# Sitara_DDR.net
KiCad netlist of a schematic drawn in Altium Designer
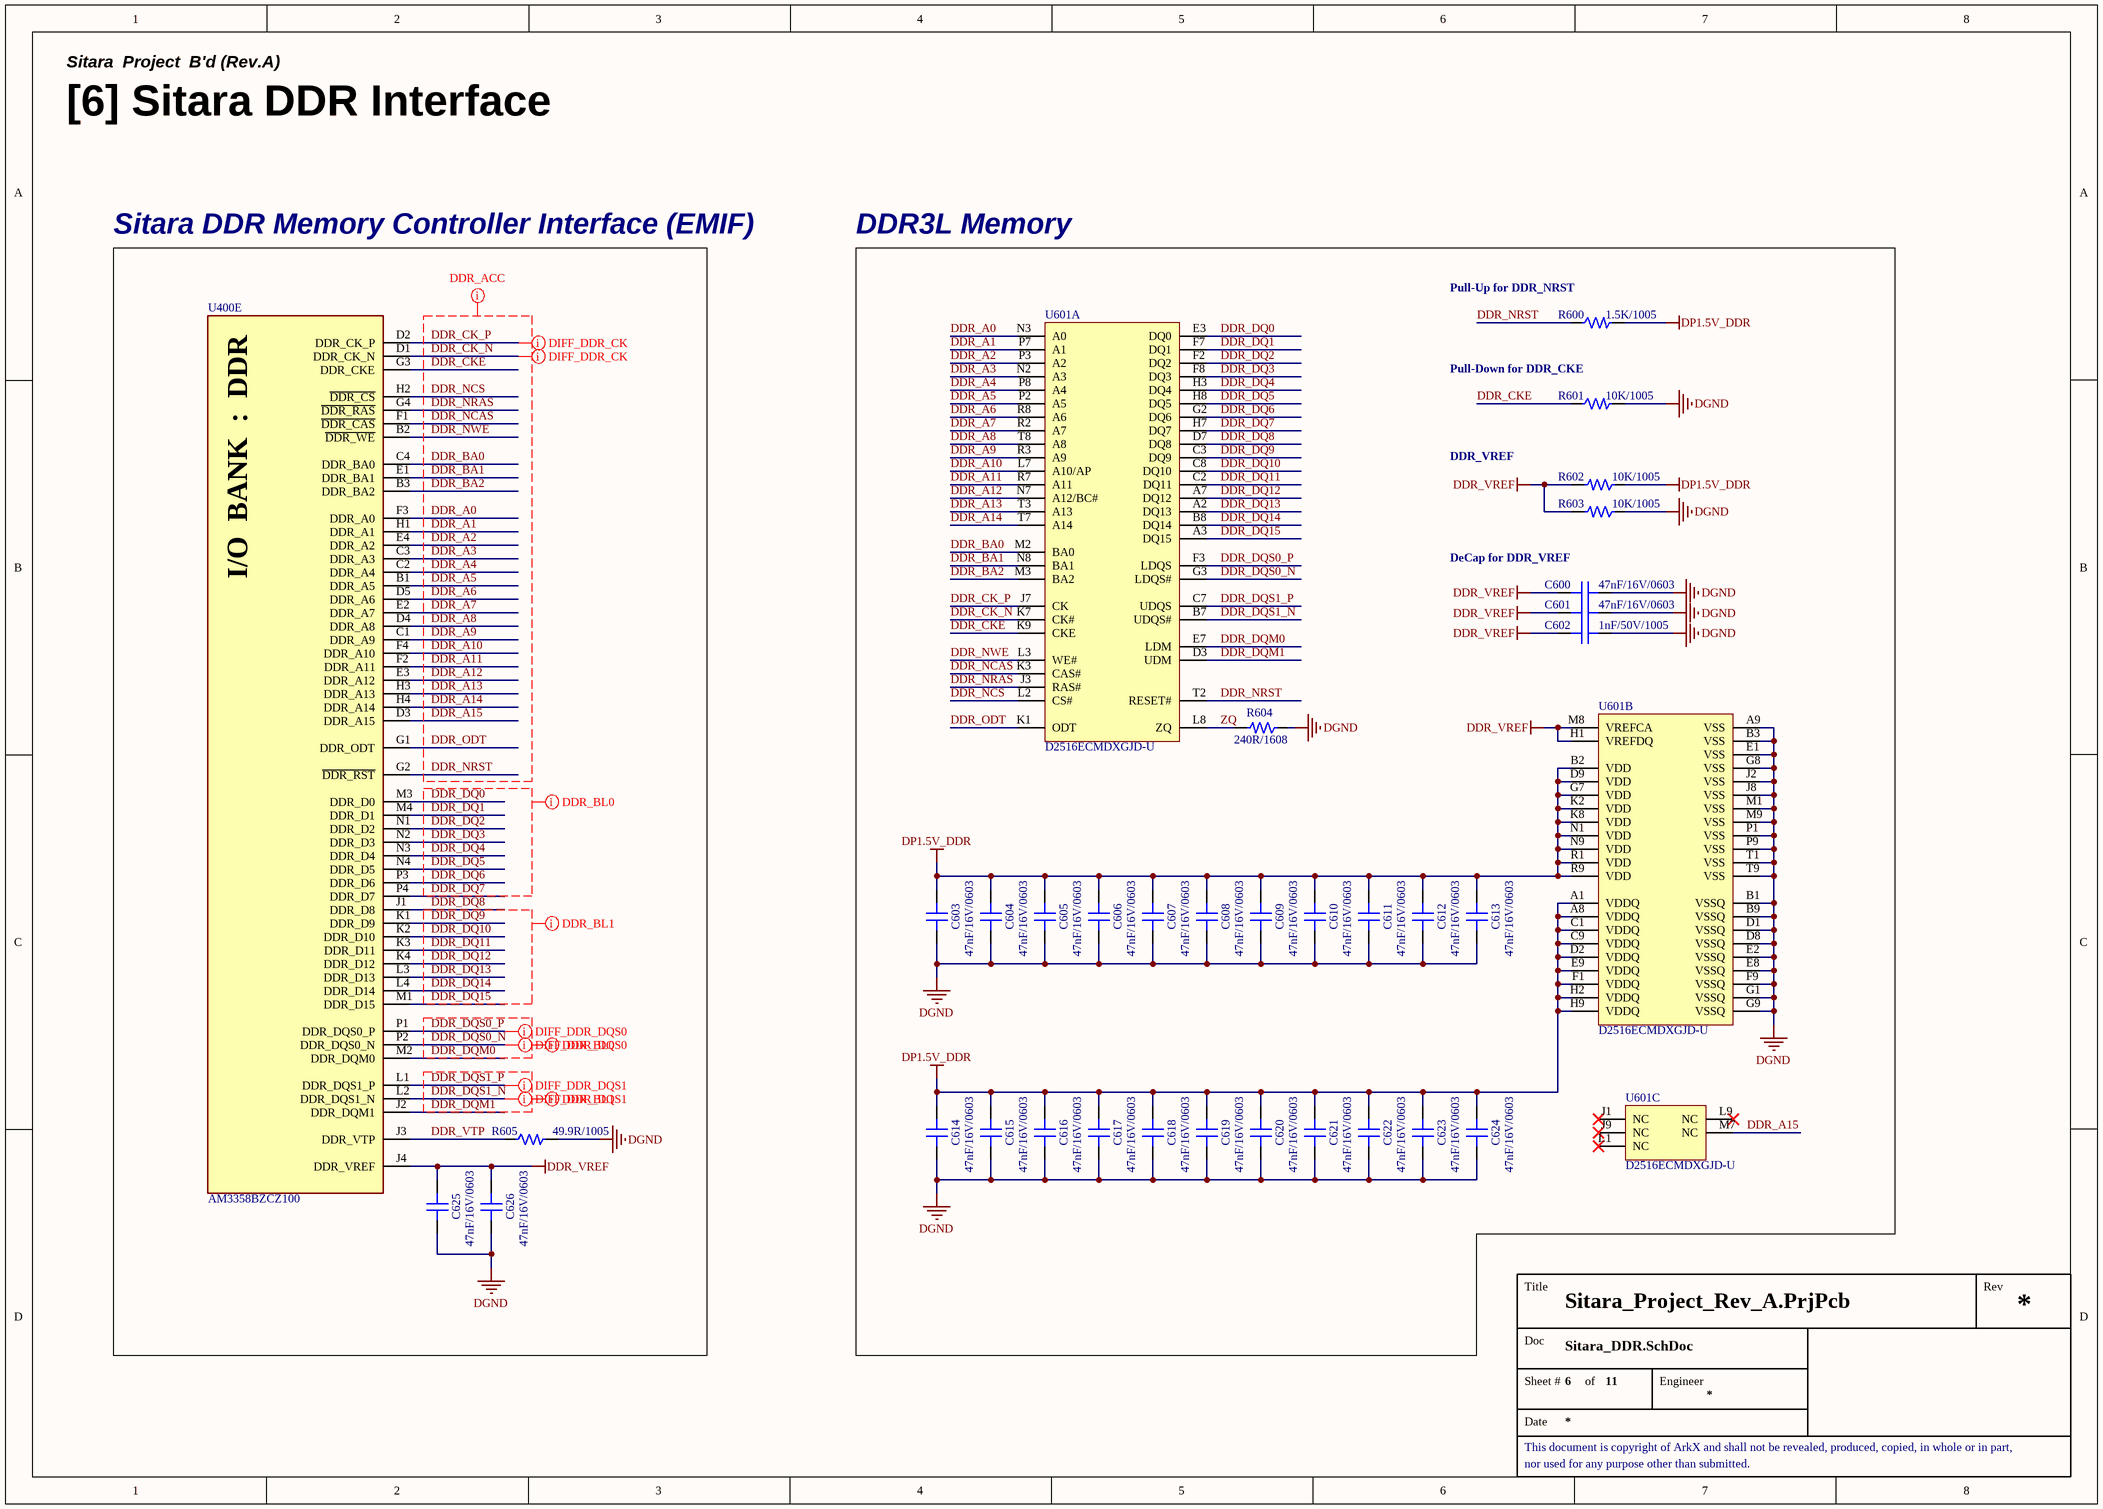
[diagram p0: Sitara_DDR.SchDoc]

(export (version "E")
  (design (tool "Eeschema 10.0.6"))
  (components
    (comp (ref "C600")
      (value "47nF/16V/0603")
      (footprint "CAP 0603 (0201_INCH)")
      (description "16V 47nF X5R ±10% 0201 Multilayer Ceramic Capacitors MLCC - SMD/SMT ROHS")
      (fields (field (name "LCSC PART #") "C88917"))
      (libsource (lib "Arkx") (part "CAP_47nF/16V/0603"))
    )
    (comp (ref "C601")
      (value "47nF/16V/0603")
      (footprint "CAP 0603 (0201_INCH)")
      (description "16V 47nF X5R ±10% 0201 Multilayer Ceramic Capacitors MLCC - SMD/SMT ROHS")
      (fields (field (name "LCSC PART #") "C88917"))
      (libsource (lib "Arkx") (part "CAP_47nF/16V/0603"))
    )
    (comp (ref "C602")
      (value "1nF/50V/1005")
      (footprint "CAP 1005 (0402_INCH)")
      (description "Ceramic CAP_1nF/50V/1005")
      (fields (field (name "LCSC PART #") "C1523"))
      (libsource (lib "Arkx") (part "CAP_1nF/50V/1005"))
    )
    (comp (ref "C603")
      (value "47nF/16V/0603")
      (footprint "CAP 0603 (0201_INCH)")
      (description "16V 47nF X5R ±10% 0201 Multilayer Ceramic Capacitors MLCC - SMD/SMT ROHS")
      (fields (field (name "LCSC PART #") "C88917"))
      (libsource (lib "Arkx") (part "CAP_47nF/16V/0603"))
    )
    (comp (ref "C604")
      (value "47nF/16V/0603")
      (footprint "CAP 0603 (0201_INCH)")
      (description "16V 47nF X5R ±10% 0201 Multilayer Ceramic Capacitors MLCC - SMD/SMT ROHS")
      (fields (field (name "LCSC PART #") "C88917"))
      (libsource (lib "Arkx") (part "CAP_47nF/16V/0603"))
    )
    (comp (ref "C605")
      (value "47nF/16V/0603")
      (footprint "CAP 0603 (0201_INCH)")
      (description "16V 47nF X5R ±10% 0201 Multilayer Ceramic Capacitors MLCC - SMD/SMT ROHS")
      (fields (field (name "LCSC PART #") "C88917"))
      (libsource (lib "Arkx") (part "CAP_47nF/16V/0603"))
    )
    (comp (ref "C606")
      (value "47nF/16V/0603")
      (footprint "CAP 0603 (0201_INCH)")
      (description "16V 47nF X5R ±10% 0201 Multilayer Ceramic Capacitors MLCC - SMD/SMT ROHS")
      (fields (field (name "LCSC PART #") "C88917"))
      (libsource (lib "Arkx") (part "CAP_47nF/16V/0603"))
    )
    (comp (ref "C607")
      (value "47nF/16V/0603")
      (footprint "CAP 0603 (0201_INCH)")
      (description "16V 47nF X5R ±10% 0201 Multilayer Ceramic Capacitors MLCC - SMD/SMT ROHS")
      (fields (field (name "LCSC PART #") "C88917"))
      (libsource (lib "Arkx") (part "CAP_47nF/16V/0603"))
    )
    (comp (ref "C608")
      (value "47nF/16V/0603")
      (footprint "CAP 0603 (0201_INCH)")
      (description "16V 47nF X5R ±10% 0201 Multilayer Ceramic Capacitors MLCC - SMD/SMT ROHS")
      (fields (field (name "LCSC PART #") "C88917"))
      (libsource (lib "Arkx") (part "CAP_47nF/16V/0603"))
    )
    (comp (ref "C609")
      (value "47nF/16V/0603")
      (footprint "CAP 0603 (0201_INCH)")
      (description "16V 47nF X5R ±10% 0201 Multilayer Ceramic Capacitors MLCC - SMD/SMT ROHS")
      (fields (field (name "LCSC PART #") "C88917"))
      (libsource (lib "Arkx") (part "CAP_47nF/16V/0603"))
    )
    (comp (ref "C610")
      (value "47nF/16V/0603")
      (footprint "CAP 0603 (0201_INCH)")
      (description "16V 47nF X5R ±10% 0201 Multilayer Ceramic Capacitors MLCC - SMD/SMT ROHS")
      (fields (field (name "LCSC PART #") "C88917"))
      (libsource (lib "Arkx") (part "CAP_47nF/16V/0603"))
    )
    (comp (ref "C611")
      (value "47nF/16V/0603")
      (footprint "CAP 0603 (0201_INCH)")
      (description "16V 47nF X5R ±10% 0201 Multilayer Ceramic Capacitors MLCC - SMD/SMT ROHS")
      (fields (field (name "LCSC PART #") "C88917"))
      (libsource (lib "Arkx") (part "CAP_47nF/16V/0603"))
    )
    (comp (ref "C612")
      (value "47nF/16V/0603")
      (footprint "CAP 0603 (0201_INCH)")
      (description "16V 47nF X5R ±10% 0201 Multilayer Ceramic Capacitors MLCC - SMD/SMT ROHS")
      (fields (field (name "LCSC PART #") "C88917"))
      (libsource (lib "Arkx") (part "CAP_47nF/16V/0603"))
    )
    (comp (ref "C613")
      (value "47nF/16V/0603")
      (footprint "CAP 0603 (0201_INCH)")
      (description "16V 47nF X5R ±10% 0201 Multilayer Ceramic Capacitors MLCC - SMD/SMT ROHS")
      (fields (field (name "LCSC PART #") "C88917"))
      (libsource (lib "Arkx") (part "CAP_47nF/16V/0603"))
    )
    (comp (ref "C614")
      (value "47nF/16V/0603")
      (footprint "CAP 0603 (0201_INCH)")
      (description "16V 47nF X5R ±10% 0201 Multilayer Ceramic Capacitors MLCC - SMD/SMT ROHS")
      (fields (field (name "LCSC PART #") "C88917"))
      (libsource (lib "Arkx") (part "CAP_47nF/16V/0603"))
    )
    (comp (ref "C615")
      (value "47nF/16V/0603")
      (footprint "CAP 0603 (0201_INCH)")
      (description "16V 47nF X5R ±10% 0201 Multilayer Ceramic Capacitors MLCC - SMD/SMT ROHS")
      (fields (field (name "LCSC PART #") "C88917"))
      (libsource (lib "Arkx") (part "CAP_47nF/16V/0603"))
    )
    (comp (ref "C616")
      (value "47nF/16V/0603")
      (footprint "CAP 0603 (0201_INCH)")
      (description "16V 47nF X5R ±10% 0201 Multilayer Ceramic Capacitors MLCC - SMD/SMT ROHS")
      (fields (field (name "LCSC PART #") "C88917"))
      (libsource (lib "Arkx") (part "CAP_47nF/16V/0603"))
    )
    (comp (ref "C617")
      (value "47nF/16V/0603")
      (footprint "CAP 0603 (0201_INCH)")
      (description "16V 47nF X5R ±10% 0201 Multilayer Ceramic Capacitors MLCC - SMD/SMT ROHS")
      (fields (field (name "LCSC PART #") "C88917"))
      (libsource (lib "Arkx") (part "CAP_47nF/16V/0603"))
    )
    (comp (ref "C618")
      (value "47nF/16V/0603")
      (footprint "CAP 0603 (0201_INCH)")
      (description "16V 47nF X5R ±10% 0201 Multilayer Ceramic Capacitors MLCC - SMD/SMT ROHS")
      (fields (field (name "LCSC PART #") "C88917"))
      (libsource (lib "Arkx") (part "CAP_47nF/16V/0603"))
    )
    (comp (ref "C619")
      (value "47nF/16V/0603")
      (footprint "CAP 0603 (0201_INCH)")
      (description "16V 47nF X5R ±10% 0201 Multilayer Ceramic Capacitors MLCC - SMD/SMT ROHS")
      (fields (field (name "LCSC PART #") "C88917"))
      (libsource (lib "Arkx") (part "CAP_47nF/16V/0603"))
    )
    (comp (ref "C620")
      (value "47nF/16V/0603")
      (footprint "CAP 0603 (0201_INCH)")
      (description "16V 47nF X5R ±10% 0201 Multilayer Ceramic Capacitors MLCC - SMD/SMT ROHS")
      (fields (field (name "LCSC PART #") "C88917"))
      (libsource (lib "Arkx") (part "CAP_47nF/16V/0603"))
    )
    (comp (ref "C621")
      (value "47nF/16V/0603")
      (footprint "CAP 0603 (0201_INCH)")
      (description "16V 47nF X5R ±10% 0201 Multilayer Ceramic Capacitors MLCC - SMD/SMT ROHS")
      (fields (field (name "LCSC PART #") "C88917"))
      (libsource (lib "Arkx") (part "CAP_47nF/16V/0603"))
    )
    (comp (ref "C622")
      (value "47nF/16V/0603")
      (footprint "CAP 0603 (0201_INCH)")
      (description "16V 47nF X5R ±10% 0201 Multilayer Ceramic Capacitors MLCC - SMD/SMT ROHS")
      (fields (field (name "LCSC PART #") "C88917"))
      (libsource (lib "Arkx") (part "CAP_47nF/16V/0603"))
    )
    (comp (ref "C623")
      (value "47nF/16V/0603")
      (footprint "CAP 0603 (0201_INCH)")
      (description "16V 47nF X5R ±10% 0201 Multilayer Ceramic Capacitors MLCC - SMD/SMT ROHS")
      (fields (field (name "LCSC PART #") "C88917"))
      (libsource (lib "Arkx") (part "CAP_47nF/16V/0603"))
    )
    (comp (ref "C624")
      (value "47nF/16V/0603")
      (footprint "CAP 0603 (0201_INCH)")
      (description "16V 47nF X5R ±10% 0201 Multilayer Ceramic Capacitors MLCC - SMD/SMT ROHS")
      (fields (field (name "LCSC PART #") "C88917"))
      (libsource (lib "Arkx") (part "CAP_47nF/16V/0603"))
    )
    (comp (ref "C625")
      (value "47nF/16V/0603")
      (footprint "CAP 0603 (0201_INCH)")
      (description "16V 47nF X5R ±10% 0201 Multilayer Ceramic Capacitors MLCC - SMD/SMT ROHS")
      (fields (field (name "LCSC PART #") "C88917"))
      (libsource (lib "Arkx") (part "CAP_47nF/16V/0603"))
    )
    (comp (ref "C626")
      (value "47nF/16V/0603")
      (footprint "CAP 0603 (0201_INCH)")
      (description "16V 47nF X5R ±10% 0201 Multilayer Ceramic Capacitors MLCC - SMD/SMT ROHS")
      (fields (field (name "LCSC PART #") "C88917"))
      (libsource (lib "Arkx") (part "CAP_47nF/16V/0603"))
    )
    (comp (ref "R600")
      (value "1.5K/1005")
      (footprint "RES 1005 (0402_inch)")
      (description "RES_1.5K/1005/62.5mW")
      (fields (field (name "LCSC PART #") "C25867"))
      (libsource (lib "Arkx") (part "RES_1.5K/1005/62.5mW"))
    )
    (comp (ref "R601")
      (value "10K/1005")
      (footprint "RES 1005 (0402_inch)")
      (description "RES_10K/1005/62.5mW")
      (fields (field (name "LCSC PART #") "C25744"))
      (libsource (lib "Arkx") (part "RES_10K/1005/62.5mW"))
    )
    (comp (ref "R602")
      (value "10K/1005")
      (footprint "RES 1005 (0402_inch)")
      (description "RES_10K/1005/62.5mW")
      (fields (field (name "LCSC PART #") "C25744"))
      (libsource (lib "Arkx") (part "RES_10K/1005/62.5mW"))
    )
    (comp (ref "R603")
      (value "10K/1005")
      (footprint "RES 1005 (0402_inch)")
      (description "RES_10K/1005/62.5mW")
      (fields (field (name "LCSC PART #") "C25744"))
      (libsource (lib "Arkx") (part "RES_10K/1005/62.5mW"))
    )
    (comp (ref "R604")
      (value "240R/1608")
      (footprint "RES 1608 (0603_inch)")
      (description "RES_240R/1608/0.1W")
      (fields (field (name "LCSC PART #") "C23350"))
      (libsource (lib "Arkx") (part "RES_240R/1608/0.1W"))
    )
    (comp (ref "R605")
      (value "49.9R/1005")
      (footprint "RES 1005 (0402_inch)")
      (description "RES_49.9R/1005/62.5mW")
      (fields (field (name "LCSC PART #") "C25120"))
      (libsource (lib "Arkx") (part "RES_49.9R/1005/62.5mW"))
    )
    (comp (ref "U400")
      (value "AM3358BZCZ100")
      (footprint "IC_SOC_AM3358BZCZ100")
      (description "ARM® Cortex®-A8 Microprocessor IC Sitara™ 1 Core, 32-Bit 1.0GHz 324-NFBGA (15x15)")
      (fields (field (name "LCSC PART #") "C73932"))
      (libsource (lib "Arkx") (part "IC_SOC_AM3358BZCZ100"))
    )
    (comp (ref "U601")
      (value "D2516ECMDXGJD-U")
      (footprint "IC_MEM_DDR3L_MT41K256M16TW-107 IT:P")
      (description "DRAM 4Gb 96 ball FBGA DDR3L 1866")
      (fields (field (name "LCSC PART #") "C2927180"))
      (libsource (lib "Arkx") (part "IC_MEM_DDR3L_D2516ECMDXGJD-U"))
    )
  )
  (nets
    (net (code "1") (name "/DDR_A0") (class "Default")
      (node (ref "U400") (pin "F3") (pinfunction "DDR_A0_F3") (pintype "passive"))
      (node (ref "U601") (pin "N3") (pinfunction "A0_N3") (pintype "passive"))
    )
    (net (code "2") (name "/DDR_A1") (class "Default")
      (node (ref "U400") (pin "H1") (pinfunction "DDR_A1_H1") (pintype "passive"))
      (node (ref "U601") (pin "P7") (pinfunction "A1_P7") (pintype "passive"))
    )
    (net (code "3") (name "/DDR_A2") (class "Default")
      (node (ref "U400") (pin "E4") (pinfunction "DDR_A2_E4") (pintype "passive"))
      (node (ref "U601") (pin "P3") (pinfunction "A2_P3") (pintype "passive"))
    )
    (net (code "4") (name "/DDR_A3") (class "Default")
      (node (ref "U400") (pin "C3") (pinfunction "DDR_A3_C3") (pintype "passive"))
      (node (ref "U601") (pin "N2") (pinfunction "A3_N2") (pintype "passive"))
    )
    (net (code "5") (name "/DDR_A4") (class "Default")
      (node (ref "U400") (pin "C2") (pinfunction "DDR_A4_C2") (pintype "passive"))
      (node (ref "U601") (pin "P8") (pinfunction "A4_P8") (pintype "passive"))
    )
    (net (code "6") (name "/DDR_A5") (class "Default")
      (node (ref "U400") (pin "B1") (pinfunction "DDR_A5_B1") (pintype "passive"))
      (node (ref "U601") (pin "P2") (pinfunction "A5_P2") (pintype "passive"))
    )
    (net (code "7") (name "/DDR_A6") (class "Default")
      (node (ref "U400") (pin "D5") (pinfunction "DDR_A6_D5") (pintype "passive"))
      (node (ref "U601") (pin "R8") (pinfunction "A6_R8") (pintype "passive"))
    )
    (net (code "8") (name "/DDR_A7") (class "Default")
      (node (ref "U400") (pin "E2") (pinfunction "DDR_A7_E2") (pintype "passive"))
      (node (ref "U601") (pin "R2") (pinfunction "A7_R2") (pintype "passive"))
    )
    (net (code "9") (name "/DDR_A8") (class "Default")
      (node (ref "U400") (pin "D4") (pinfunction "DDR_A8_D4") (pintype "passive"))
      (node (ref "U601") (pin "T8") (pinfunction "A8_T8") (pintype "passive"))
    )
    (net (code "10") (name "/DDR_A9") (class "Default")
      (node (ref "U400") (pin "C1") (pinfunction "DDR_A9_C1") (pintype "passive"))
      (node (ref "U601") (pin "R3") (pinfunction "A9_R3") (pintype "passive"))
    )
    (net (code "11") (name "/DDR_A10") (class "Default")
      (node (ref "U400") (pin "F4") (pinfunction "DDR_A10_F4") (pintype "passive"))
      (node (ref "U601") (pin "L7") (pinfunction "A10/AP_L7") (pintype "passive"))
    )
    (net (code "12") (name "/DDR_A11") (class "Default")
      (node (ref "U400") (pin "F2") (pinfunction "DDR_A11_F2") (pintype "passive"))
      (node (ref "U601") (pin "R7") (pinfunction "A11_R7") (pintype "passive"))
    )
    (net (code "13") (name "/DDR_A12") (class "Default")
      (node (ref "U400") (pin "E3") (pinfunction "DDR_A12_E3") (pintype "passive"))
      (node (ref "U601") (pin "N7") (pinfunction "A12/BC#_N7") (pintype "passive"))
    )
    (net (code "14") (name "/DDR_A13") (class "Default")
      (node (ref "U400") (pin "H3") (pinfunction "DDR_A13_H3") (pintype "passive"))
      (node (ref "U601") (pin "T3") (pinfunction "A13_T3") (pintype "passive"))
    )
    (net (code "15") (name "/DDR_A14") (class "Default")
      (node (ref "U400") (pin "H4") (pinfunction "DDR_A14_H4") (pintype "passive"))
      (node (ref "U601") (pin "T7") (pinfunction "A14_T7") (pintype "passive"))
    )
    (net (code "16") (name "/DDR_A15") (class "Default")
      (node (ref "U400") (pin "D3") (pinfunction "DDR_A15_D3") (pintype "passive"))
      (node (ref "U601") (pin "M7") (pinfunction "NC_M7") (pintype "passive"))
    )
    (net (code "17") (name "/DDR_BA0") (class "Default")
      (node (ref "U400") (pin "C4") (pinfunction "DDR_BA0_C4") (pintype "passive"))
      (node (ref "U601") (pin "M2") (pinfunction "BA0_M2") (pintype "passive"))
    )
    (net (code "18") (name "/DDR_BA1") (class "Default")
      (node (ref "U400") (pin "E1") (pinfunction "DDR_BA1_E1") (pintype "passive"))
      (node (ref "U601") (pin "N8") (pinfunction "BA1_N8") (pintype "passive"))
    )
    (net (code "19") (name "/DDR_BA2") (class "Default")
      (node (ref "U400") (pin "B3") (pinfunction "DDR_BA2_B3") (pintype "passive"))
      (node (ref "U601") (pin "M3") (pinfunction "BA2_M3") (pintype "passive"))
    )
    (net (code "20") (name "/DDR_CKE") (class "Default")
      (node (ref "R601") (pin "1") (pinfunction "1_1") (pintype "passive"))
      (node (ref "U400") (pin "G3") (pinfunction "DDR_CKE_G3") (pintype "passive"))
      (node (ref "U601") (pin "K9") (pinfunction "CKE_K9") (pintype "passive"))
    )
    (net (code "21") (name "/DDR_CK_N") (class "Default")
      (node (ref "U400") (pin "D1") (pinfunction "DDR_CK_N_D1") (pintype "passive"))
      (node (ref "U601") (pin "K7") (pinfunction "CK#_K7") (pintype "passive"))
    )
    (net (code "22") (name "/DDR_CK_P") (class "Default")
      (node (ref "U400") (pin "D2") (pinfunction "DDR_CK_P_D2") (pintype "passive"))
      (node (ref "U601") (pin "J7") (pinfunction "CK_J7") (pintype "passive"))
    )
    (net (code "23") (name "/DDR_DQ0") (class "Default")
      (node (ref "U400") (pin "M3") (pinfunction "DDR_D0_M3") (pintype "passive"))
      (node (ref "U601") (pin "E3") (pinfunction "DQ0_E3") (pintype "passive"))
    )
    (net (code "24") (name "/DDR_DQ1") (class "Default")
      (node (ref "U400") (pin "M4") (pinfunction "DDR_D1_M4") (pintype "passive"))
      (node (ref "U601") (pin "F7") (pinfunction "DQ1_F7") (pintype "passive"))
    )
    (net (code "25") (name "/DDR_DQ2") (class "Default")
      (node (ref "U400") (pin "N1") (pinfunction "DDR_D2_N1") (pintype "passive"))
      (node (ref "U601") (pin "F2") (pinfunction "DQ2_F2") (pintype "passive"))
    )
    (net (code "26") (name "/DDR_DQ3") (class "Default")
      (node (ref "U400") (pin "N2") (pinfunction "DDR_D3_N2") (pintype "passive"))
      (node (ref "U601") (pin "F8") (pinfunction "DQ3_F8") (pintype "passive"))
    )
    (net (code "27") (name "/DDR_DQ4") (class "Default")
      (node (ref "U400") (pin "N3") (pinfunction "DDR_D4_N3") (pintype "passive"))
      (node (ref "U601") (pin "H3") (pinfunction "DQ4_H3") (pintype "passive"))
    )
    (net (code "28") (name "/DDR_DQ5") (class "Default")
      (node (ref "U400") (pin "N4") (pinfunction "DDR_D5_N4") (pintype "passive"))
      (node (ref "U601") (pin "H8") (pinfunction "DQ5_H8") (pintype "passive"))
    )
    (net (code "29") (name "/DDR_DQ6") (class "Default")
      (node (ref "U400") (pin "P3") (pinfunction "DDR_D6_P3") (pintype "passive"))
      (node (ref "U601") (pin "G2") (pinfunction "DQ6_G2") (pintype "passive"))
    )
    (net (code "30") (name "/DDR_DQ7") (class "Default")
      (node (ref "U400") (pin "P4") (pinfunction "DDR_D7_P4") (pintype "passive"))
      (node (ref "U601") (pin "H7") (pinfunction "DQ7_H7") (pintype "passive"))
    )
    (net (code "31") (name "/DDR_DQ8") (class "Default")
      (node (ref "U400") (pin "J1") (pinfunction "DDR_D8_J1") (pintype "passive"))
      (node (ref "U601") (pin "D7") (pinfunction "DQ8_D7") (pintype "passive"))
    )
    (net (code "32") (name "/DDR_DQ9") (class "Default")
      (node (ref "U400") (pin "K1") (pinfunction "DDR_D9_K1") (pintype "passive"))
      (node (ref "U601") (pin "C3") (pinfunction "DQ9_C3") (pintype "passive"))
    )
    (net (code "33") (name "/DDR_DQ10") (class "Default")
      (node (ref "U400") (pin "K2") (pinfunction "DDR_D10_K2") (pintype "passive"))
      (node (ref "U601") (pin "C8") (pinfunction "DQ10_C8") (pintype "passive"))
    )
    (net (code "34") (name "/DDR_DQ11") (class "Default")
      (node (ref "U400") (pin "K3") (pinfunction "DDR_D11_K3") (pintype "passive"))
      (node (ref "U601") (pin "C2") (pinfunction "DQ11_C2") (pintype "passive"))
    )
    (net (code "35") (name "/DDR_DQ12") (class "Default")
      (node (ref "U400") (pin "K4") (pinfunction "DDR_D12_K4") (pintype "passive"))
      (node (ref "U601") (pin "A7") (pinfunction "DQ12_A7") (pintype "passive"))
    )
    (net (code "36") (name "/DDR_DQ13") (class "Default")
      (node (ref "U400") (pin "L3") (pinfunction "DDR_D13_L3") (pintype "passive"))
      (node (ref "U601") (pin "A2") (pinfunction "DQ13_A2") (pintype "passive"))
    )
    (net (code "37") (name "/DDR_DQ14") (class "Default")
      (node (ref "U400") (pin "L4") (pinfunction "DDR_D14_L4") (pintype "passive"))
      (node (ref "U601") (pin "B8") (pinfunction "DQ14_B8") (pintype "passive"))
    )
    (net (code "38") (name "/DDR_DQ15") (class "Default")
      (node (ref "U400") (pin "M1") (pinfunction "DDR_D15_M1") (pintype "passive"))
      (node (ref "U601") (pin "A3") (pinfunction "DQ15_A3") (pintype "passive"))
    )
    (net (code "39") (name "/DDR_DQM0") (class "Default")
      (node (ref "U400") (pin "M2") (pinfunction "DDR_DQM0_M2") (pintype "passive"))
      (node (ref "U601") (pin "E7") (pinfunction "LDM_E7") (pintype "passive"))
    )
    (net (code "40") (name "/DDR_DQM1") (class "Default")
      (node (ref "U400") (pin "J2") (pinfunction "DDR_DQM1_J2") (pintype "passive"))
      (node (ref "U601") (pin "D3") (pinfunction "UDM_D3") (pintype "passive"))
    )
    (net (code "41") (name "/DDR_DQS0_N") (class "Default")
      (node (ref "U400") (pin "P2") (pinfunction "DDR_DQS0_N_P2") (pintype "passive"))
      (node (ref "U601") (pin "G3") (pinfunction "LDQS#_G3") (pintype "passive"))
    )
    (net (code "42") (name "/DDR_DQS0_P") (class "Default")
      (node (ref "U400") (pin "P1") (pinfunction "DDR_DQS0_P_P1") (pintype "passive"))
      (node (ref "U601") (pin "F3") (pinfunction "LDQS_F3") (pintype "passive"))
    )
    (net (code "43") (name "/DDR_DQS1_N") (class "Default")
      (node (ref "U400") (pin "L2") (pinfunction "DDR_DQS1_N_L2") (pintype "passive"))
      (node (ref "U601") (pin "B7") (pinfunction "UDQS#_B7") (pintype "passive"))
    )
    (net (code "44") (name "/DDR_DQS1_P") (class "Default")
      (node (ref "U400") (pin "L1") (pinfunction "DDR_DQS1_P_L1") (pintype "passive"))
      (node (ref "U601") (pin "C7") (pinfunction "UDQS_C7") (pintype "passive"))
    )
    (net (code "45") (name "/DDR_NCAS") (class "Default")
      (node (ref "U400") (pin "F1") (pinfunction "~{DDR_CAS}_F1") (pintype "passive"))
      (node (ref "U601") (pin "K3") (pinfunction "CAS#_K3") (pintype "passive"))
    )
    (net (code "46") (name "/DDR_NCS") (class "Default")
      (node (ref "U400") (pin "H2") (pinfunction "~{DDR_CS}_H2") (pintype "passive"))
      (node (ref "U601") (pin "L2") (pinfunction "CS#_L2") (pintype "passive"))
    )
    (net (code "47") (name "/DDR_NRAS") (class "Default")
      (node (ref "U400") (pin "G4") (pinfunction "~{DDR_RAS}_G4") (pintype "passive"))
      (node (ref "U601") (pin "J3") (pinfunction "RAS#_J3") (pintype "passive"))
    )
    (net (code "48") (name "/DDR_NRST") (class "Default")
      (node (ref "R600") (pin "1") (pinfunction "1_1") (pintype "passive"))
      (node (ref "U400") (pin "G2") (pinfunction "~{DDR_RST}_G2") (pintype "passive"))
      (node (ref "U601") (pin "T2") (pinfunction "RESET#_T2") (pintype "passive"))
    )
    (net (code "49") (name "/DDR_NWE") (class "Default")
      (node (ref "U400") (pin "B2") (pinfunction "~{DDR_WE}_B2") (pintype "passive"))
      (node (ref "U601") (pin "L3") (pinfunction "WE#_L3") (pintype "passive"))
    )
    (net (code "50") (name "/DDR_ODT") (class "Default")
      (node (ref "U400") (pin "G1") (pinfunction "DDR_ODT_G1") (pintype "passive"))
      (node (ref "U601") (pin "K1") (pinfunction "ODT_K1") (pintype "passive"))
    )
    (net (code "51") (name "/DDR_VTP") (class "Default")
      (node (ref "R605") (pin "1") (pinfunction "1_1") (pintype "passive"))
      (node (ref "U400") (pin "J3") (pinfunction "DDR_VTP_J3") (pintype "passive"))
    )
    (net (code "52") (name "/ZQ") (class "Default")
      (node (ref "R604") (pin "2") (pinfunction "2_2") (pintype "passive"))
      (node (ref "U601") (pin "L8") (pinfunction "ZQ_L8") (pintype "passive"))
    )
    (net (code "53") (name "DDR_VREF") (class "Default")
      (node (ref "C600") (pin "2") (pinfunction "2_2") (pintype "passive"))
      (node (ref "C601") (pin "2") (pinfunction "2_2") (pintype "passive"))
      (node (ref "C602") (pin "2") (pinfunction "2_2") (pintype "passive"))
      (node (ref "C625") (pin "2") (pinfunction "2_2") (pintype "passive"))
      (node (ref "C626") (pin "2") (pinfunction "2_2") (pintype "passive"))
      (node (ref "R602") (pin "2") (pinfunction "2_2") (pintype "passive"))
      (node (ref "R603") (pin "2") (pinfunction "2_2") (pintype "passive"))
      (node (ref "U400") (pin "J4") (pinfunction "DDR_VREF_J4") (pintype "passive"))
      (node (ref "U601") (pin "H1") (pinfunction "VREFDQ_H1") (pintype "passive"))
      (node (ref "U601") (pin "M8") (pinfunction "VREFCA_M8") (pintype "passive"))
    )
    (net (code "54") (name "DGND") (class "Default")
      (node (ref "C600") (pin "1") (pinfunction "1_1") (pintype "passive"))
      (node (ref "C601") (pin "1") (pinfunction "1_1") (pintype "passive"))
      (node (ref "C602") (pin "1") (pinfunction "1_1") (pintype "passive"))
      (node (ref "C603") (pin "1") (pinfunction "1_1") (pintype "passive"))
      (node (ref "C604") (pin "1") (pinfunction "1_1") (pintype "passive"))
      (node (ref "C605") (pin "1") (pinfunction "1_1") (pintype "passive"))
      (node (ref "C606") (pin "1") (pinfunction "1_1") (pintype "passive"))
      (node (ref "C607") (pin "1") (pinfunction "1_1") (pintype "passive"))
      (node (ref "C608") (pin "1") (pinfunction "1_1") (pintype "passive"))
      (node (ref "C609") (pin "1") (pinfunction "1_1") (pintype "passive"))
      (node (ref "C610") (pin "1") (pinfunction "1_1") (pintype "passive"))
      (node (ref "C611") (pin "1") (pinfunction "1_1") (pintype "passive"))
      (node (ref "C612") (pin "1") (pinfunction "1_1") (pintype "passive"))
      (node (ref "C613") (pin "1") (pinfunction "1_1") (pintype "passive"))
      (node (ref "C614") (pin "1") (pinfunction "1_1") (pintype "passive"))
      (node (ref "C615") (pin "1") (pinfunction "1_1") (pintype "passive"))
      (node (ref "C616") (pin "1") (pinfunction "1_1") (pintype "passive"))
      (node (ref "C617") (pin "1") (pinfunction "1_1") (pintype "passive"))
      (node (ref "C618") (pin "1") (pinfunction "1_1") (pintype "passive"))
      (node (ref "C619") (pin "1") (pinfunction "1_1") (pintype "passive"))
      (node (ref "C620") (pin "1") (pinfunction "1_1") (pintype "passive"))
      (node (ref "C621") (pin "1") (pinfunction "1_1") (pintype "passive"))
      (node (ref "C622") (pin "1") (pinfunction "1_1") (pintype "passive"))
      (node (ref "C623") (pin "1") (pinfunction "1_1") (pintype "passive"))
      (node (ref "C624") (pin "1") (pinfunction "1_1") (pintype "passive"))
      (node (ref "C625") (pin "1") (pinfunction "1_1") (pintype "passive"))
      (node (ref "C626") (pin "1") (pinfunction "1_1") (pintype "passive"))
      (node (ref "R601") (pin "2") (pinfunction "2_2") (pintype "passive"))
      (node (ref "R603") (pin "1") (pinfunction "1_1") (pintype "passive"))
      (node (ref "R604") (pin "1") (pinfunction "1_1") (pintype "passive"))
      (node (ref "R605") (pin "2") (pinfunction "2_2") (pintype "passive"))
      (node (ref "U601") (pin "A9") (pinfunction "VSS_A9") (pintype "passive"))
      (node (ref "U601") (pin "B1") (pinfunction "VSSQ_B1") (pintype "passive"))
      (node (ref "U601") (pin "B3") (pinfunction "VSS_B3") (pintype "passive"))
      (node (ref "U601") (pin "B9") (pinfunction "VSSQ_B9") (pintype "passive"))
      (node (ref "U601") (pin "D1") (pinfunction "VSSQ_D1") (pintype "passive"))
      (node (ref "U601") (pin "D8") (pinfunction "VSSQ_D8") (pintype "passive"))
      (node (ref "U601") (pin "E1") (pinfunction "VSS_E1") (pintype "passive"))
      (node (ref "U601") (pin "E2") (pinfunction "VSSQ_E2") (pintype "passive"))
      (node (ref "U601") (pin "E8") (pinfunction "VSSQ_E8") (pintype "passive"))
      (node (ref "U601") (pin "F9") (pinfunction "VSSQ_F9") (pintype "passive"))
      (node (ref "U601") (pin "G1") (pinfunction "VSSQ_G1") (pintype "passive"))
      (node (ref "U601") (pin "G8") (pinfunction "VSS_G8") (pintype "passive"))
      (node (ref "U601") (pin "G9") (pinfunction "VSSQ_G9") (pintype "passive"))
      (node (ref "U601") (pin "J2") (pinfunction "VSS_J2") (pintype "passive"))
      (node (ref "U601") (pin "J8") (pinfunction "VSS_J8") (pintype "passive"))
      (node (ref "U601") (pin "M1") (pinfunction "VSS_M1") (pintype "passive"))
      (node (ref "U601") (pin "M9") (pinfunction "VSS_M9") (pintype "passive"))
      (node (ref "U601") (pin "P1") (pinfunction "VSS_P1") (pintype "passive"))
      (node (ref "U601") (pin "P9") (pinfunction "VSS_P9") (pintype "passive"))
      (node (ref "U601") (pin "T1") (pinfunction "VSS_T1") (pintype "passive"))
      (node (ref "U601") (pin "T9") (pinfunction "VSS_T9") (pintype "passive"))
    )
    (net (code "55") (name "DP1.5V_DDR") (class "Default")
      (node (ref "C603") (pin "2") (pinfunction "2_2") (pintype "passive"))
      (node (ref "C604") (pin "2") (pinfunction "2_2") (pintype "passive"))
      (node (ref "C605") (pin "2") (pinfunction "2_2") (pintype "passive"))
      (node (ref "C606") (pin "2") (pinfunction "2_2") (pintype "passive"))
      (node (ref "C607") (pin "2") (pinfunction "2_2") (pintype "passive"))
      (node (ref "C608") (pin "2") (pinfunction "2_2") (pintype "passive"))
      (node (ref "C609") (pin "2") (pinfunction "2_2") (pintype "passive"))
      (node (ref "C610") (pin "2") (pinfunction "2_2") (pintype "passive"))
      (node (ref "C611") (pin "2") (pinfunction "2_2") (pintype "passive"))
      (node (ref "C612") (pin "2") (pinfunction "2_2") (pintype "passive"))
      (node (ref "C613") (pin "2") (pinfunction "2_2") (pintype "passive"))
      (node (ref "C614") (pin "2") (pinfunction "2_2") (pintype "passive"))
      (node (ref "C615") (pin "2") (pinfunction "2_2") (pintype "passive"))
      (node (ref "C616") (pin "2") (pinfunction "2_2") (pintype "passive"))
      (node (ref "C617") (pin "2") (pinfunction "2_2") (pintype "passive"))
      (node (ref "C618") (pin "2") (pinfunction "2_2") (pintype "passive"))
      (node (ref "C619") (pin "2") (pinfunction "2_2") (pintype "passive"))
      (node (ref "C620") (pin "2") (pinfunction "2_2") (pintype "passive"))
      (node (ref "C621") (pin "2") (pinfunction "2_2") (pintype "passive"))
      (node (ref "C622") (pin "2") (pinfunction "2_2") (pintype "passive"))
      (node (ref "C623") (pin "2") (pinfunction "2_2") (pintype "passive"))
      (node (ref "C624") (pin "2") (pinfunction "2_2") (pintype "passive"))
      (node (ref "R600") (pin "2") (pinfunction "2_2") (pintype "passive"))
      (node (ref "R602") (pin "1") (pinfunction "1_1") (pintype "passive"))
      (node (ref "U601") (pin "A1") (pinfunction "VDDQ_A1") (pintype "passive"))
      (node (ref "U601") (pin "A8") (pinfunction "VDDQ_A8") (pintype "passive"))
      (node (ref "U601") (pin "B2") (pinfunction "VDD_B2") (pintype "passive"))
      (node (ref "U601") (pin "C1") (pinfunction "VDDQ_C1") (pintype "passive"))
      (node (ref "U601") (pin "C9") (pinfunction "VDDQ_C9") (pintype "passive"))
      (node (ref "U601") (pin "D2") (pinfunction "VDDQ_D2") (pintype "passive"))
      (node (ref "U601") (pin "D9") (pinfunction "VDD_D9") (pintype "passive"))
      (node (ref "U601") (pin "E9") (pinfunction "VDDQ_E9") (pintype "passive"))
      (node (ref "U601") (pin "F1") (pinfunction "VDDQ_F1") (pintype "passive"))
      (node (ref "U601") (pin "G7") (pinfunction "VDD_G7") (pintype "passive"))
      (node (ref "U601") (pin "H2") (pinfunction "VDDQ_H2") (pintype "passive"))
      (node (ref "U601") (pin "H9") (pinfunction "VDDQ_H9") (pintype "passive"))
      (node (ref "U601") (pin "K2") (pinfunction "VDD_K2") (pintype "passive"))
      (node (ref "U601") (pin "K8") (pinfunction "VDD_K8") (pintype "passive"))
      (node (ref "U601") (pin "N1") (pinfunction "VDD_N1") (pintype "passive"))
      (node (ref "U601") (pin "N9") (pinfunction "VDD_N9") (pintype "passive"))
      (node (ref "U601") (pin "R1") (pinfunction "VDD_R1") (pintype "passive"))
      (node (ref "U601") (pin "R9") (pinfunction "VDD_R9") (pintype "passive"))
    )
    (net (code "56") (name "unconnected-(U601C-NC-PadJ1)") (class "Default")
      (node (ref "U601") (pin "J1") (pinfunction "NC_J1") (pintype "passive+no_connect"))
    )
    (net (code "57") (name "unconnected-(U601C-NC-PadJ9)") (class "Default")
      (node (ref "U601") (pin "J9") (pinfunction "NC_J9") (pintype "passive+no_connect"))
    )
    (net (code "58") (name "unconnected-(U601C-NC-PadL1)") (class "Default")
      (node (ref "U601") (pin "L1") (pinfunction "NC_L1") (pintype "passive+no_connect"))
    )
    (net (code "59") (name "unconnected-(U601C-NC-PadL9)") (class "Default")
      (node (ref "U601") (pin "L9") (pinfunction "NC_L9") (pintype "passive+no_connect"))
    )
  )
)
